# track-hold-sampler.net
KiCad netlist of a schematic drawn in EAGLE
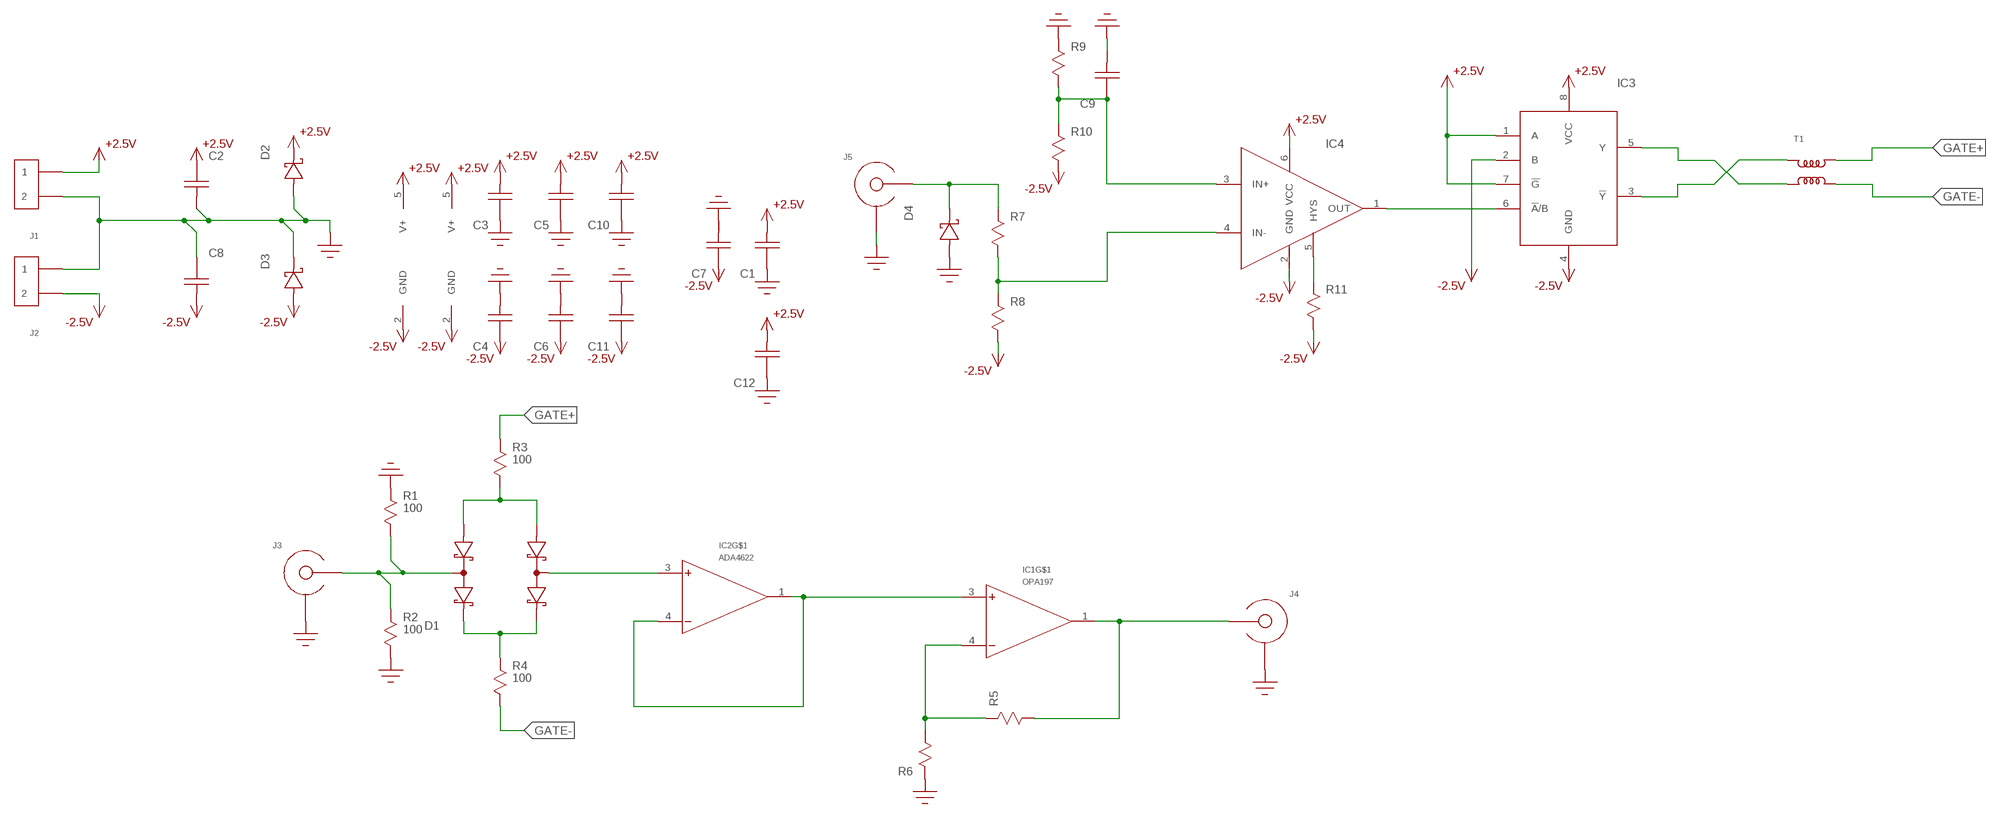
[diagram p0: schematic, sheet 1]

(export (version "E")
  (design (tool "Eeschema 10.0.6"))
  (components
    (comp (ref "C1")
      (value "C0603")
      (footprint "eagle-import:C0603")
      (libsource (lib "eagle-import") (part "C0603"))
    )
    (comp (ref "C2")
      (value "C1206")
      (footprint "eagle-import:1206")
      (libsource (lib "eagle-import") (part "C1206"))
    )
    (comp (ref "C3") (value "C") (footprint "eagle-import:C0402") (libsource (lib "eagle-import") (part "C")))
    (comp (ref "C4") (value "C") (footprint "eagle-import:C0402") (libsource (lib "eagle-import") (part "C")))
    (comp (ref "C5") (value "C") (footprint "eagle-import:C0402") (libsource (lib "eagle-import") (part "C")))
    (comp (ref "C6") (value "C") (footprint "eagle-import:C0402") (libsource (lib "eagle-import") (part "C")))
    (comp (ref "C7")
      (value "C0603")
      (footprint "eagle-import:C0603")
      (libsource (lib "eagle-import") (part "C0603"))
    )
    (comp (ref "C8")
      (value "C1206")
      (footprint "eagle-import:1206")
      (libsource (lib "eagle-import") (part "C1206"))
    )
    (comp (ref "C9") (value "C") (footprint "eagle-import:C0402") (libsource (lib "eagle-import") (part "C")))
    (comp (ref "C10")
      (value "C")
      (footprint "eagle-import:C0402")
      (libsource (lib "eagle-import") (part "C"))
    )
    (comp (ref "C11")
      (value "C")
      (footprint "eagle-import:C0402")
      (libsource (lib "eagle-import") (part "C"))
    )
    (comp (ref "C12")
      (value "C0603")
      (footprint "eagle-import:C0603")
      (libsource (lib "eagle-import") (part "C0603"))
    )
    (comp (ref "D1")
      (value "SMS3923-081")
      (footprint "eagle-import:SC-88")
      (libsource (lib "eagle-import") (part "SMS3923-081"))
    )
    (comp (ref "D2")
      (value "SCHOTTKYSOT-23")
      (footprint "eagle-import:SOT-23")
      (libsource (lib "eagle-import") (part "SCHOTTKYSOT-23"))
    )
    (comp (ref "D3")
      (value "SCHOTTKYSOT-23")
      (footprint "eagle-import:SOT-23")
      (libsource (lib "eagle-import") (part "SCHOTTKYSOT-23"))
    )
    (comp (ref "D4")
      (value "SCHOTTKYSOT-23")
      (footprint "eagle-import:SOT-23")
      (libsource (lib "eagle-import") (part "SCHOTTKYSOT-23"))
    )
    (comp (ref "IC1")
      (value "OPA197")
      (footprint "eagle-import:TSOT-23")
      (libsource (lib "eagle-import") (part "OPA197TSOT"))
    )
    (comp (ref "IC2")
      (value "ADA4622")
      (footprint "eagle-import:SOT23-5")
      (libsource (lib "eagle-import") (part "ADA4622"))
    )
    (comp (ref "IC3")
      (value "74LVC2G157")
      (footprint "eagle-import:SSOP8")
      (libsource (lib "eagle-import") (part "74LVC2G157"))
    )
    (comp (ref "IC4")
      (value "ADCMP601")
      (footprint "eagle-import:SC70-6")
      (libsource (lib "eagle-import") (part "ADCMP601"))
    )
    (comp (ref "J1")
      (value "HEADER_2PIN")
      (footprint "eagle-import:HEADER_2PIN")
      (libsource (lib "eagle-import") (part "HEADER_2PIN"))
    )
    (comp (ref "J2")
      (value "HEADER_2PIN")
      (footprint "eagle-import:HEADER_2PIN")
      (libsource (lib "eagle-import") (part "HEADER_2PIN"))
    )
    (comp (ref "J3")
      (value "SMA-EDGE-LAUNCH4020N5")
      (footprint "eagle-import:SMA_EDGE_LAUNCH_4L_4020_N5")
      (libsource (lib "eagle-import") (part "SMA-EDGE-LAUNCH4020N5"))
    )
    (comp (ref "J4")
      (value "SMA-EDGE-LAUNCH4020N5")
      (footprint "eagle-import:SMA_EDGE_LAUNCH_4L_4020_N5")
      (libsource (lib "eagle-import") (part "SMA-EDGE-LAUNCH4020N5"))
    )
    (comp (ref "J5")
      (value "SMA-EDGE-LAUNCH4020N5")
      (footprint "eagle-import:SMA_EDGE_LAUNCH_4L_4020_N5")
      (libsource (lib "eagle-import") (part "SMA-EDGE-LAUNCH4020N5"))
    )
    (comp (ref "R1")
      (value "100")
      (footprint "eagle-import:0402")
      (libsource (lib "eagle-import") (part "R0402"))
    )
    (comp (ref "R2")
      (value "100")
      (footprint "eagle-import:0402")
      (libsource (lib "eagle-import") (part "R0402"))
    )
    (comp (ref "R3")
      (value "100")
      (footprint "eagle-import:0402")
      (libsource (lib "eagle-import") (part "R0402"))
    )
    (comp (ref "R4")
      (value "100")
      (footprint "eagle-import:0402")
      (libsource (lib "eagle-import") (part "R0402"))
    )
    (comp (ref "R5")
      (value "R0603")
      (footprint "eagle-import:R0603")
      (libsource (lib "eagle-import") (part "R0603"))
    )
    (comp (ref "R6")
      (value "R0603")
      (footprint "eagle-import:R0603")
      (libsource (lib "eagle-import") (part "R0603"))
    )
    (comp (ref "R7")
      (value "R0603")
      (footprint "eagle-import:R0603")
      (libsource (lib "eagle-import") (part "R0603"))
    )
    (comp (ref "R8")
      (value "R0603")
      (footprint "eagle-import:R0603")
      (libsource (lib "eagle-import") (part "R0603"))
    )
    (comp (ref "R9")
      (value "R0603")
      (footprint "eagle-import:R0603")
      (libsource (lib "eagle-import") (part "R0603"))
    )
    (comp (ref "R10")
      (value "R0603")
      (footprint "eagle-import:R0603")
      (libsource (lib "eagle-import") (part "R0603"))
    )
    (comp (ref "R11")
      (value "R0603")
      (footprint "eagle-import:R0603")
      (libsource (lib "eagle-import") (part "R0603"))
    )
    (comp (ref "T1")
      (value "MABA007159")
      (footprint "eagle-import:MABAES0061")
      (libsource (lib "eagle-import") (part "MABA007159"))
    )
  )
  (nets
    (net (code "1") (name "+2.5V") (class "Default")
      (node (ref "C1") (pin "P$1") (pinfunction "P$1_P$1") (pintype "bidirectional"))
      (node (ref "C10") (pin "1") (pinfunction "P$1_1") (pintype "bidirectional"))
      (node (ref "C12") (pin "P$1") (pinfunction "P$1_P$1") (pintype "bidirectional"))
      (node (ref "C2") (pin "P$2") (pinfunction "P$2_P$2") (pintype "bidirectional"))
      (node (ref "C3") (pin "1") (pinfunction "P$1_1") (pintype "bidirectional"))
      (node (ref "C5") (pin "1") (pinfunction "P$1_1") (pintype "bidirectional"))
      (node (ref "D2") (pin "3") (pinfunction "CATHODE_3") (pintype "bidirectional"))
      (node (ref "IC1") (pin "5") (pinfunction "V+_5") (pintype "bidirectional"))
      (node (ref "IC2") (pin "5") (pinfunction "V+_5") (pintype "bidirectional"))
      (node (ref "IC3") (pin "1") (pinfunction "A_1") (pintype "bidirectional"))
      (node (ref "IC3") (pin "7") (pinfunction "~{G}_7") (pintype "bidirectional"))
      (node (ref "IC3") (pin "8") (pinfunction "VCC_8") (pintype "bidirectional"))
      (node (ref "IC4") (pin "6") (pinfunction "VCC_6") (pintype "bidirectional"))
      (node (ref "J1") (pin "1") (pinfunction "1_1") (pintype "bidirectional"))
    )
    (net (code "2") (name "-2.5V") (class "Default")
      (node (ref "C11") (pin "2") (pinfunction "P$2_2") (pintype "bidirectional"))
      (node (ref "C4") (pin "2") (pinfunction "P$2_2") (pintype "bidirectional"))
      (node (ref "C6") (pin "2") (pinfunction "P$2_2") (pintype "bidirectional"))
      (node (ref "C7") (pin "P$2") (pinfunction "P$2_P$2") (pintype "bidirectional"))
      (node (ref "C8") (pin "P$1") (pinfunction "P$1_P$1") (pintype "bidirectional"))
      (node (ref "D3") (pin "1") (pinfunction "ANODE_1") (pintype "bidirectional"))
      (node (ref "IC1") (pin "2") (pinfunction "GND_2") (pintype "bidirectional"))
      (node (ref "IC2") (pin "2") (pinfunction "GND_2") (pintype "bidirectional"))
      (node (ref "IC3") (pin "2") (pinfunction "B_2") (pintype "bidirectional"))
      (node (ref "IC3") (pin "4") (pinfunction "GND_4") (pintype "bidirectional"))
      (node (ref "IC4") (pin "2") (pinfunction "GND_2") (pintype "bidirectional"))
      (node (ref "J2") (pin "2") (pinfunction "2_2") (pintype "bidirectional"))
      (node (ref "R10") (pin "P$2") (pinfunction "P$4_P$2") (pintype "bidirectional"))
      (node (ref "R11") (pin "P$2") (pinfunction "P$4_P$2") (pintype "bidirectional"))
      (node (ref "R8") (pin "P$2") (pinfunction "P$4_P$2") (pintype "bidirectional"))
    )
    (net (code "3") (name "GATE+") (class "Default")
      (node (ref "R3") (pin "1") (pinfunction "P$3_1") (pintype "bidirectional"))
      (node (ref "T1") (pin "1") (pinfunction "1_1") (pintype "bidirectional"))
    )
    (net (code "4") (name "GATE-") (class "Default")
      (node (ref "R4") (pin "2") (pinfunction "P$4_2") (pintype "bidirectional"))
      (node (ref "T1") (pin "3") (pinfunction "3_3") (pintype "bidirectional"))
    )
    (net (code "5") (name "GND") (class "Default")
      (node (ref "C1") (pin "P$2") (pinfunction "P$2_P$2") (pintype "bidirectional"))
      (node (ref "C10") (pin "2") (pinfunction "P$2_2") (pintype "bidirectional"))
      (node (ref "C11") (pin "1") (pinfunction "P$1_1") (pintype "bidirectional"))
      (node (ref "C12") (pin "P$2") (pinfunction "P$2_P$2") (pintype "bidirectional"))
      (node (ref "C2") (pin "P$1") (pinfunction "P$1_P$1") (pintype "bidirectional"))
      (node (ref "C3") (pin "2") (pinfunction "P$2_2") (pintype "bidirectional"))
      (node (ref "C4") (pin "1") (pinfunction "P$1_1") (pintype "bidirectional"))
      (node (ref "C5") (pin "2") (pinfunction "P$2_2") (pintype "bidirectional"))
      (node (ref "C6") (pin "1") (pinfunction "P$1_1") (pintype "bidirectional"))
      (node (ref "C7") (pin "P$1") (pinfunction "P$1_P$1") (pintype "bidirectional"))
      (node (ref "C8") (pin "P$2") (pinfunction "P$2_P$2") (pintype "bidirectional"))
      (node (ref "C9") (pin "1") (pinfunction "P$1_1") (pintype "bidirectional"))
      (node (ref "D2") (pin "1") (pinfunction "ANODE_1") (pintype "bidirectional"))
      (node (ref "D3") (pin "3") (pinfunction "CATHODE_3") (pintype "bidirectional"))
      (node (ref "D4") (pin "1") (pinfunction "ANODE_1") (pintype "bidirectional"))
      (node (ref "J1") (pin "2") (pinfunction "2_2") (pintype "bidirectional"))
      (node (ref "J2") (pin "1") (pinfunction "1_1") (pintype "bidirectional"))
      (node (ref "J3") (pin "BOTTOM_GND") (pinfunction "SHIELD_BOTTOM_GND") (pintype "bidirectional"))
      (node (ref "J3") (pin "GND@1") (pinfunction "SHIELD_GND@1") (pintype "bidirectional"))
      (node (ref "J3") (pin "GND@10") (pinfunction "SHIELD_GND@10") (pintype "bidirectional"))
      (node (ref "J3") (pin "GND@14") (pinfunction "SHIELD_GND@14") (pintype "bidirectional"))
      (node (ref "J3") (pin "GND@15") (pinfunction "SHIELD_GND@15") (pintype "bidirectional"))
      (node (ref "J3") (pin "GND@16") (pinfunction "SHIELD_GND@16") (pintype "bidirectional"))
      (node (ref "J3") (pin "GND@17") (pinfunction "SHIELD_GND@17") (pintype "bidirectional"))
      (node (ref "J3") (pin "GND@2") (pinfunction "SHIELD_GND@2") (pintype "bidirectional"))
      (node (ref "J3") (pin "GND@3") (pinfunction "SHIELD_GND@3") (pintype "bidirectional"))
      (node (ref "J3") (pin "GND@4") (pinfunction "SHIELD_GND@4") (pintype "bidirectional"))
      (node (ref "J3") (pin "GND@5") (pinfunction "SHIELD_GND@5") (pintype "bidirectional"))
      (node (ref "J3") (pin "GND@6") (pinfunction "SHIELD_GND@6") (pintype "bidirectional"))
      (node (ref "J3") (pin "GND@7") (pinfunction "SHIELD_GND@7") (pintype "bidirectional"))
      (node (ref "J3") (pin "GND@8") (pinfunction "SHIELD_GND@8") (pintype "bidirectional"))
      (node (ref "J3") (pin "GND@9") (pinfunction "SHIELD_GND@9") (pintype "bidirectional"))
      (node (ref "J3") (pin "GND_PAD1") (pinfunction "SHIELD_GND_PAD1") (pintype "bidirectional"))
      (node (ref "J3") (pin "GND_PAD2") (pinfunction "SHIELD_GND_PAD2") (pintype "bidirectional"))
      (node (ref "J3") (pin "P$1") (pinfunction "SHIELD_P$1") (pintype "bidirectional"))
      (node (ref "J3") (pin "P$2") (pinfunction "SHIELD_P$2") (pintype "bidirectional"))
      (node (ref "J3") (pin "P$3") (pinfunction "SHIELD_P$3") (pintype "bidirectional"))
      (node (ref "J3") (pin "P$4") (pinfunction "SHIELD_P$4") (pintype "bidirectional"))
      (node (ref "J3") (pin "P$5") (pinfunction "SHIELD_P$5") (pintype "bidirectional"))
      (node (ref "J4") (pin "BOTTOM_GND") (pinfunction "SHIELD_BOTTOM_GND") (pintype "bidirectional"))
      (node (ref "J4") (pin "GND@1") (pinfunction "SHIELD_GND@1") (pintype "bidirectional"))
      (node (ref "J4") (pin "GND@10") (pinfunction "SHIELD_GND@10") (pintype "bidirectional"))
      (node (ref "J4") (pin "GND@14") (pinfunction "SHIELD_GND@14") (pintype "bidirectional"))
      (node (ref "J4") (pin "GND@15") (pinfunction "SHIELD_GND@15") (pintype "bidirectional"))
      (node (ref "J4") (pin "GND@16") (pinfunction "SHIELD_GND@16") (pintype "bidirectional"))
      (node (ref "J4") (pin "GND@17") (pinfunction "SHIELD_GND@17") (pintype "bidirectional"))
      (node (ref "J4") (pin "GND@2") (pinfunction "SHIELD_GND@2") (pintype "bidirectional"))
      (node (ref "J4") (pin "GND@3") (pinfunction "SHIELD_GND@3") (pintype "bidirectional"))
      (node (ref "J4") (pin "GND@4") (pinfunction "SHIELD_GND@4") (pintype "bidirectional"))
      (node (ref "J4") (pin "GND@5") (pinfunction "SHIELD_GND@5") (pintype "bidirectional"))
      (node (ref "J4") (pin "GND@6") (pinfunction "SHIELD_GND@6") (pintype "bidirectional"))
      (node (ref "J4") (pin "GND@7") (pinfunction "SHIELD_GND@7") (pintype "bidirectional"))
      (node (ref "J4") (pin "GND@8") (pinfunction "SHIELD_GND@8") (pintype "bidirectional"))
      (node (ref "J4") (pin "GND@9") (pinfunction "SHIELD_GND@9") (pintype "bidirectional"))
      (node (ref "J4") (pin "GND_PAD1") (pinfunction "SHIELD_GND_PAD1") (pintype "bidirectional"))
      (node (ref "J4") (pin "GND_PAD2") (pinfunction "SHIELD_GND_PAD2") (pintype "bidirectional"))
      (node (ref "J4") (pin "P$1") (pinfunction "SHIELD_P$1") (pintype "bidirectional"))
      (node (ref "J4") (pin "P$2") (pinfunction "SHIELD_P$2") (pintype "bidirectional"))
      (node (ref "J4") (pin "P$3") (pinfunction "SHIELD_P$3") (pintype "bidirectional"))
      (node (ref "J4") (pin "P$4") (pinfunction "SHIELD_P$4") (pintype "bidirectional"))
      (node (ref "J4") (pin "P$5") (pinfunction "SHIELD_P$5") (pintype "bidirectional"))
      (node (ref "J5") (pin "BOTTOM_GND") (pinfunction "SHIELD_BOTTOM_GND") (pintype "bidirectional"))
      (node (ref "J5") (pin "GND@1") (pinfunction "SHIELD_GND@1") (pintype "bidirectional"))
      (node (ref "J5") (pin "GND@10") (pinfunction "SHIELD_GND@10") (pintype "bidirectional"))
      (node (ref "J5") (pin "GND@14") (pinfunction "SHIELD_GND@14") (pintype "bidirectional"))
      (node (ref "J5") (pin "GND@15") (pinfunction "SHIELD_GND@15") (pintype "bidirectional"))
      (node (ref "J5") (pin "GND@16") (pinfunction "SHIELD_GND@16") (pintype "bidirectional"))
      (node (ref "J5") (pin "GND@17") (pinfunction "SHIELD_GND@17") (pintype "bidirectional"))
      (node (ref "J5") (pin "GND@2") (pinfunction "SHIELD_GND@2") (pintype "bidirectional"))
      (node (ref "J5") (pin "GND@3") (pinfunction "SHIELD_GND@3") (pintype "bidirectional"))
      (node (ref "J5") (pin "GND@4") (pinfunction "SHIELD_GND@4") (pintype "bidirectional"))
      (node (ref "J5") (pin "GND@5") (pinfunction "SHIELD_GND@5") (pintype "bidirectional"))
      (node (ref "J5") (pin "GND@6") (pinfunction "SHIELD_GND@6") (pintype "bidirectional"))
      (node (ref "J5") (pin "GND@7") (pinfunction "SHIELD_GND@7") (pintype "bidirectional"))
      (node (ref "J5") (pin "GND@8") (pinfunction "SHIELD_GND@8") (pintype "bidirectional"))
      (node (ref "J5") (pin "GND@9") (pinfunction "SHIELD_GND@9") (pintype "bidirectional"))
      (node (ref "J5") (pin "GND_PAD1") (pinfunction "SHIELD_GND_PAD1") (pintype "bidirectional"))
      (node (ref "J5") (pin "GND_PAD2") (pinfunction "SHIELD_GND_PAD2") (pintype "bidirectional"))
      (node (ref "J5") (pin "P$1") (pinfunction "SHIELD_P$1") (pintype "bidirectional"))
      (node (ref "J5") (pin "P$2") (pinfunction "SHIELD_P$2") (pintype "bidirectional"))
      (node (ref "J5") (pin "P$3") (pinfunction "SHIELD_P$3") (pintype "bidirectional"))
      (node (ref "J5") (pin "P$4") (pinfunction "SHIELD_P$4") (pintype "bidirectional"))
      (node (ref "J5") (pin "P$5") (pinfunction "SHIELD_P$5") (pintype "bidirectional"))
      (node (ref "R1") (pin "1") (pinfunction "P$3_1") (pintype "bidirectional"))
      (node (ref "R2") (pin "2") (pinfunction "P$4_2") (pintype "bidirectional"))
      (node (ref "R6") (pin "P$1") (pinfunction "P$3_P$1") (pintype "bidirectional"))
      (node (ref "R9") (pin "P$1") (pinfunction "P$3_P$1") (pintype "bidirectional"))
    )
    (net (code "6") (name "Net-(C9-P$2)") (class "Default")
      (node (ref "C9") (pin "2") (pinfunction "P$2_2") (pintype "bidirectional"))
      (node (ref "IC4") (pin "3") (pinfunction "IN+_3") (pintype "bidirectional"))
      (node (ref "R10") (pin "P$1") (pinfunction "P$3_P$1") (pintype "bidirectional"))
      (node (ref "R9") (pin "P$2") (pinfunction "P$4_P$2") (pintype "bidirectional"))
    )
    (net (code "7") (name "Net-(D1-ANODE0)") (class "Default")
      (node (ref "D1") (pin "1") (pinfunction "ANODE0_1") (pintype "bidirectional"))
      (node (ref "D1") (pin "6") (pinfunction "ANODE1_6") (pintype "bidirectional"))
      (node (ref "R3") (pin "2") (pinfunction "P$4_2") (pintype "bidirectional"))
    )
    (net (code "8") (name "Net-(D1-CATHODE0)") (class "Default")
      (node (ref "D1") (pin "3") (pinfunction "CATHODE0_3") (pintype "bidirectional"))
      (node (ref "D1") (pin "4") (pinfunction "CATHODE1_4") (pintype "bidirectional"))
      (node (ref "R4") (pin "1") (pinfunction "P$3_1") (pintype "bidirectional"))
    )
    (net (code "9") (name "Net-(D1-COMMON0)") (class "Default")
      (node (ref "D1") (pin "2") (pinfunction "COMMON0_2") (pintype "bidirectional"))
      (node (ref "J3") (pin "CENTER@1") (pinfunction "CENTER_CENTER@1") (pintype "bidirectional"))
      (node (ref "J3") (pin "CENTER@2") (pinfunction "CENTER_CENTER@2") (pintype "bidirectional"))
      (node (ref "R1") (pin "2") (pinfunction "P$4_2") (pintype "bidirectional"))
      (node (ref "R2") (pin "1") (pinfunction "P$3_1") (pintype "bidirectional"))
    )
    (net (code "10") (name "Net-(D1-COMMON1)") (class "Default")
      (node (ref "D1") (pin "5") (pinfunction "COMMON1_5") (pintype "bidirectional"))
      (node (ref "IC2") (pin "3") (pinfunction "+_3") (pintype "bidirectional"))
    )
    (net (code "11") (name "Net-(D4-CATHODE)") (class "Default")
      (node (ref "D4") (pin "3") (pinfunction "CATHODE_3") (pintype "bidirectional"))
      (node (ref "J5") (pin "CENTER@1") (pinfunction "CENTER_CENTER@1") (pintype "bidirectional"))
      (node (ref "J5") (pin "CENTER@2") (pinfunction "CENTER_CENTER@2") (pintype "bidirectional"))
      (node (ref "R7") (pin "P$1") (pinfunction "P$3_P$1") (pintype "bidirectional"))
    )
    (net (code "12") (name "Net-(IC1A-+)") (class "Default")
      (node (ref "IC1") (pin "3") (pinfunction "+_3") (pintype "bidirectional"))
      (node (ref "IC2") (pin "1") (pinfunction "OUT_1") (pintype "bidirectional"))
      (node (ref "IC2") (pin "4") (pinfunction "-_4") (pintype "bidirectional"))
    )
    (net (code "13") (name "Net-(IC1A--)") (class "Default")
      (node (ref "IC1") (pin "4") (pinfunction "-_4") (pintype "bidirectional"))
      (node (ref "R5") (pin "P$1") (pinfunction "P$3_P$1") (pintype "bidirectional"))
      (node (ref "R6") (pin "P$2") (pinfunction "P$4_P$2") (pintype "bidirectional"))
    )
    (net (code "14") (name "Net-(IC1A-OUT)") (class "Default")
      (node (ref "IC1") (pin "1") (pinfunction "OUT_1") (pintype "bidirectional"))
      (node (ref "J4") (pin "CENTER@1") (pinfunction "CENTER_CENTER@1") (pintype "bidirectional"))
      (node (ref "J4") (pin "CENTER@2") (pinfunction "CENTER_CENTER@2") (pintype "bidirectional"))
      (node (ref "R5") (pin "P$2") (pinfunction "P$4_P$2") (pintype "bidirectional"))
    )
    (net (code "15") (name "Net-(IC3-Y)") (class "Default")
      (node (ref "IC3") (pin "5") (pinfunction "Y_5") (pintype "bidirectional"))
      (node (ref "T1") (pin "4") (pinfunction "4_4") (pintype "bidirectional"))
    )
    (net (code "16") (name "Net-(IC3-~{A}{slash}B)") (class "Default")
      (node (ref "IC3") (pin "6") (pinfunction "~{A}/B_6") (pintype "bidirectional"))
      (node (ref "IC4") (pin "1") (pinfunction "OUT_1") (pintype "bidirectional"))
    )
    (net (code "17") (name "Net-(IC3-~{Y})") (class "Default")
      (node (ref "IC3") (pin "3") (pinfunction "~{Y}_3") (pintype "bidirectional"))
      (node (ref "T1") (pin "5") (pinfunction "5_5") (pintype "bidirectional"))
    )
    (net (code "18") (name "Net-(IC4-HYS)") (class "Default")
      (node (ref "IC4") (pin "5") (pinfunction "HYS_5") (pintype "bidirectional"))
      (node (ref "R11") (pin "P$1") (pinfunction "P$3_P$1") (pintype "bidirectional"))
    )
    (net (code "19") (name "Net-(IC4-IN-)") (class "Default")
      (node (ref "IC4") (pin "4") (pinfunction "IN-_4") (pintype "bidirectional"))
      (node (ref "R7") (pin "P$2") (pinfunction "P$4_P$2") (pintype "bidirectional"))
      (node (ref "R8") (pin "P$1") (pinfunction "P$3_P$1") (pintype "bidirectional"))
    )
  )
)
